# LB_BIT_w15-NOR-v03_1_2.net
KiCad netlist of a schematic drawn in EAGLE
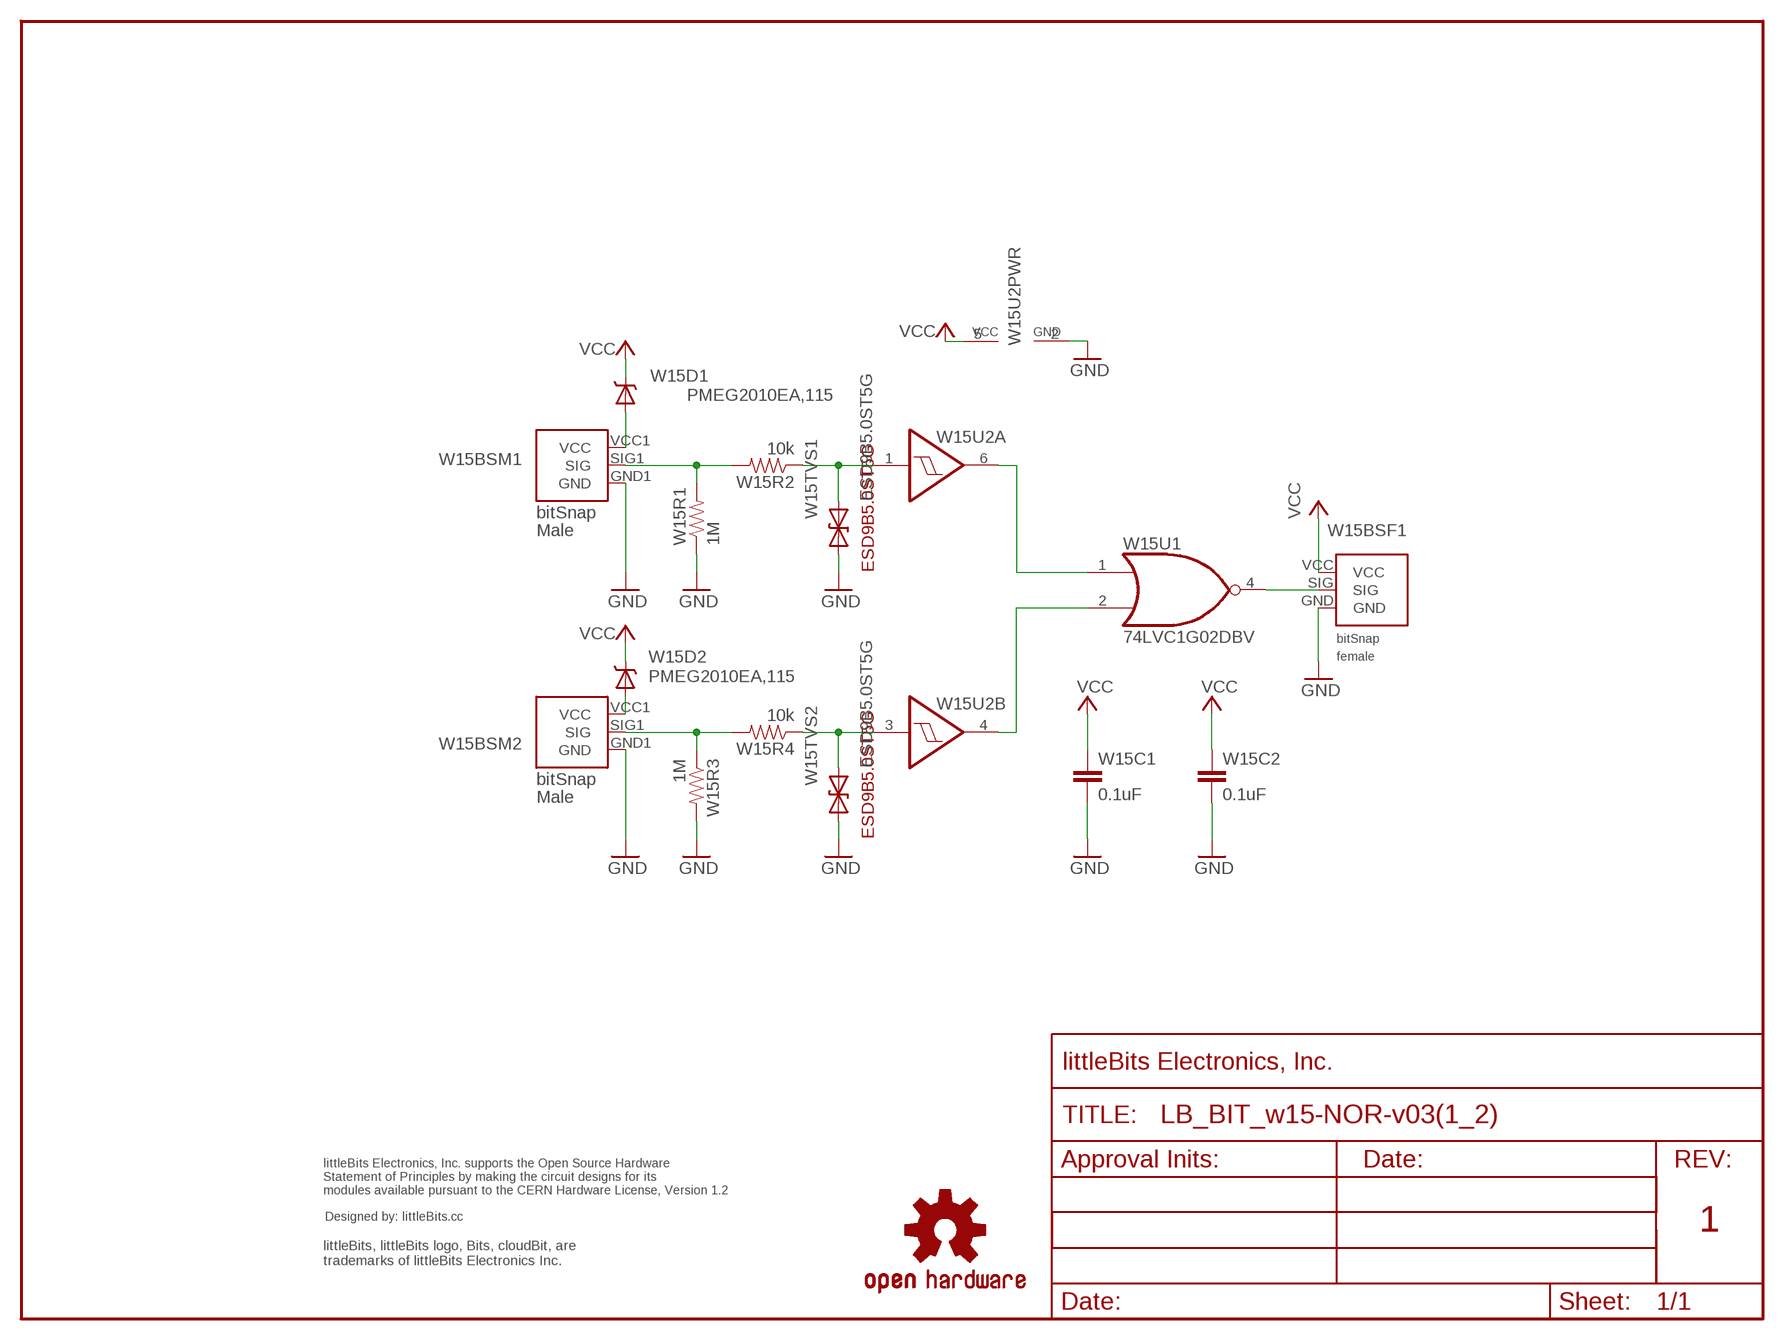
[diagram p0: schematic, sheet 1]

(export (version "E")
  (design (tool "Eeschema 10.0.6"))
  (components
    (comp (ref "U$1")
      (value "OSHWCREDIT")
      (footprint "eagle-import:OSHWCREDIT")
      (libsource (lib "eagle-import") (part "OSHWCREDIT"))
    )
    (comp (ref "U$2")
      (value "OSHW-LOGOL")
      (footprint "eagle-import:OSHW-LOGO-L")
      (libsource (lib "eagle-import") (part "OSHW-LOGOL"))
    )
    (comp (ref "U$7")
      (value "FRAME-LETTER-OHWOHW")
      (footprint "eagle-import:FABDWG01-OHW")
      (libsource (lib "eagle-import") (part "FRAME-LETTER-OHWOHW"))
    )
    (comp (ref "W15BSF1")
      (value "BITSNAP_V03_FEMALE")
      (footprint "eagle-import:BITSNAP_V03_FEMALE")
      (libsource (lib "eagle-import") (part "BITSNAP_V03_FEMALE"))
    )
    (comp (ref "W15BSM1")
      (value "BITSNAP_V03_MALE")
      (footprint "eagle-import:BITSNAP_V03_MALE")
      (libsource (lib "eagle-import") (part "BITSNAP_V03_MALE"))
    )
    (comp (ref "W15BSM2")
      (value "BITSNAP_V03_MALE")
      (footprint "eagle-import:BITSNAP_V03_MALE")
      (libsource (lib "eagle-import") (part "BITSNAP_V03_MALE"))
    )
    (comp (ref "W15C1")
      (value "0.1uF")
      (footprint "eagle-import:CAP-0603")
      (libsource (lib "eagle-import") (part "CAPCAP-0603"))
    )
    (comp (ref "W15C2")
      (value "0.1uF")
      (footprint "eagle-import:CAP-0603")
      (libsource (lib "eagle-import") (part "CAPCAP-0603"))
    )
    (comp (ref "W15D1")
      (value "PMEG2010EA,115")
      (footprint "eagle-import:SOD-323")
      (libsource (lib "eagle-import") (part "DIODE-SCHOTTKY"))
    )
    (comp (ref "W15D2")
      (value "PMEG2010EA,115")
      (footprint "eagle-import:SOD-323")
      (libsource (lib "eagle-import") (part "DIODE-SCHOTTKY"))
    )
    (comp (ref "W15R1")
      (value "1M")
      (footprint "eagle-import:0603-RES")
      (libsource (lib "eagle-import") (part "RESISTOR0603-RES"))
    )
    (comp (ref "W15R2")
      (value "10k")
      (footprint "eagle-import:0603-RES")
      (libsource (lib "eagle-import") (part "RESISTOR0603-RES"))
    )
    (comp (ref "W15R3")
      (value "1M")
      (footprint "eagle-import:0603-RES")
      (libsource (lib "eagle-import") (part "RESISTOR0603-RES"))
    )
    (comp (ref "W15R4")
      (value "10k")
      (footprint "eagle-import:0603-RES")
      (libsource (lib "eagle-import") (part "RESISTOR0603-RES"))
    )
    (comp (ref "W15TVS1")
      (value "ESD9B5.0ST5G")
      (footprint "eagle-import:SOD-923")
      (libsource (lib "eagle-import") (part "DIODE-TVSSOD-923"))
    )
    (comp (ref "W15TVS2")
      (value "ESD9B5.0ST5G")
      (footprint "eagle-import:SOD-923")
      (libsource (lib "eagle-import") (part "DIODE-TVSSOD-923"))
    )
    (comp (ref "W15U1")
      (value "74LVC1G02DBV")
      (footprint "eagle-import:SOT23-5")
      (libsource (lib "eagle-import") (part "741G02DBVLVC"))
    )
    (comp (ref "W15U2")
      (value "NC7WZ17")
      (footprint "eagle-import:SC70-6")
      (libsource (lib "eagle-import") (part "SCHMITT_TRIGGER_NON_INVERTINGNC7WZ17"))
    )
  )
  (nets
    (net (code "1") (name "GND") (class "Default")
      (node (ref "W15BSF1") (pin "GND") (pinfunction "GND_GND") (pintype "bidirectional"))
      (node (ref "W15BSM1") (pin "GND1") (pinfunction "GND_GND1") (pintype "bidirectional"))
      (node (ref "W15BSM2") (pin "GND1") (pinfunction "GND_GND1") (pintype "bidirectional"))
      (node (ref "W15C1") (pin "2") (pinfunction "2_2") (pintype "passive"))
      (node (ref "W15C2") (pin "2") (pinfunction "2_2") (pintype "passive"))
      (node (ref "W15R1") (pin "1") (pinfunction "1_1") (pintype "passive"))
      (node (ref "W15R3") (pin "2") (pinfunction "2_2") (pintype "passive"))
      (node (ref "W15TVS1") (pin "1") (pinfunction "A_1") (pintype "passive"))
      (node (ref "W15TVS2") (pin "1") (pinfunction "A_1") (pintype "passive"))
      (node (ref "W15U2") (pin "2") (pinfunction "GND_2") (pintype "power_in"))
    )
    (net (code "2") (name "Net-(W15BSM1-SIG)") (class "Default")
      (node (ref "W15BSM1") (pin "SIG1") (pinfunction "SIG_SIG1") (pintype "bidirectional"))
      (node (ref "W15R1") (pin "2") (pinfunction "2_2") (pintype "passive"))
      (node (ref "W15R2") (pin "2") (pinfunction "2_2") (pintype "passive"))
    )
    (net (code "3") (name "Net-(W15BSM1-VCC)") (class "Default")
      (node (ref "W15BSM1") (pin "VCC1") (pinfunction "VCC_VCC1") (pintype "bidirectional"))
      (node (ref "W15D1") (pin "2") (pinfunction "A_2") (pintype "passive"))
    )
    (net (code "4") (name "Net-(W15BSM2-SIG)") (class "Default")
      (node (ref "W15BSM2") (pin "SIG1") (pinfunction "SIG_SIG1") (pintype "bidirectional"))
      (node (ref "W15R3") (pin "1") (pinfunction "1_1") (pintype "passive"))
      (node (ref "W15R4") (pin "2") (pinfunction "2_2") (pintype "passive"))
    )
    (net (code "5") (name "Net-(W15BSM2-VCC)") (class "Default")
      (node (ref "W15BSM2") (pin "VCC1") (pinfunction "VCC_VCC1") (pintype "bidirectional"))
      (node (ref "W15D2") (pin "2") (pinfunction "A_2") (pintype "passive"))
    )
    (net (code "6") (name "Net-(W15TVS1-C)") (class "Default")
      (node (ref "W15R2") (pin "1") (pinfunction "1_1") (pintype "passive"))
      (node (ref "W15TVS1") (pin "2") (pinfunction "C_2") (pintype "passive"))
      (node (ref "W15U2") (pin "1") (pinfunction "I_1") (pintype "input"))
    )
    (net (code "7") (name "Net-(W15TVS2-C)") (class "Default")
      (node (ref "W15R4") (pin "1") (pinfunction "1_1") (pintype "passive"))
      (node (ref "W15TVS2") (pin "2") (pinfunction "C_2") (pintype "passive"))
      (node (ref "W15U2") (pin "3") (pinfunction "I_3") (pintype "input"))
    )
    (net (code "8") (name "Net-(W15U1A-I0)") (class "Default")
      (node (ref "W15U1") (pin "1") (pinfunction "I0_1") (pintype "input"))
      (node (ref "W15U2") (pin "6") (pinfunction "O_6") (pintype "output"))
    )
    (net (code "9") (name "Net-(W15U1A-I1)") (class "Default")
      (node (ref "W15U1") (pin "2") (pinfunction "I1_2") (pintype "input"))
      (node (ref "W15U2") (pin "4") (pinfunction "O_4") (pintype "output"))
    )
    (net (code "10") (name "Net-(W15U1A-O)") (class "Default")
      (node (ref "W15BSF1") (pin "SIG") (pinfunction "SIG_SIG") (pintype "bidirectional"))
      (node (ref "W15U1") (pin "4") (pinfunction "O_4") (pintype "output"))
    )
    (net (code "11") (name "VCC") (class "Default")
      (node (ref "W15BSF1") (pin "VCC") (pinfunction "VCC_VCC") (pintype "bidirectional"))
      (node (ref "W15C1") (pin "1") (pinfunction "1_1") (pintype "passive"))
      (node (ref "W15C2") (pin "1") (pinfunction "1_1") (pintype "passive"))
      (node (ref "W15D1") (pin "1") (pinfunction "C_1") (pintype "passive"))
      (node (ref "W15D2") (pin "1") (pinfunction "C_1") (pintype "passive"))
      (node (ref "W15U2") (pin "5") (pinfunction "VCC_5") (pintype "power_in"))
    )
  )
)
